# 3_Communication.net
KiCad netlist of a schematic drawn in Altium Designer
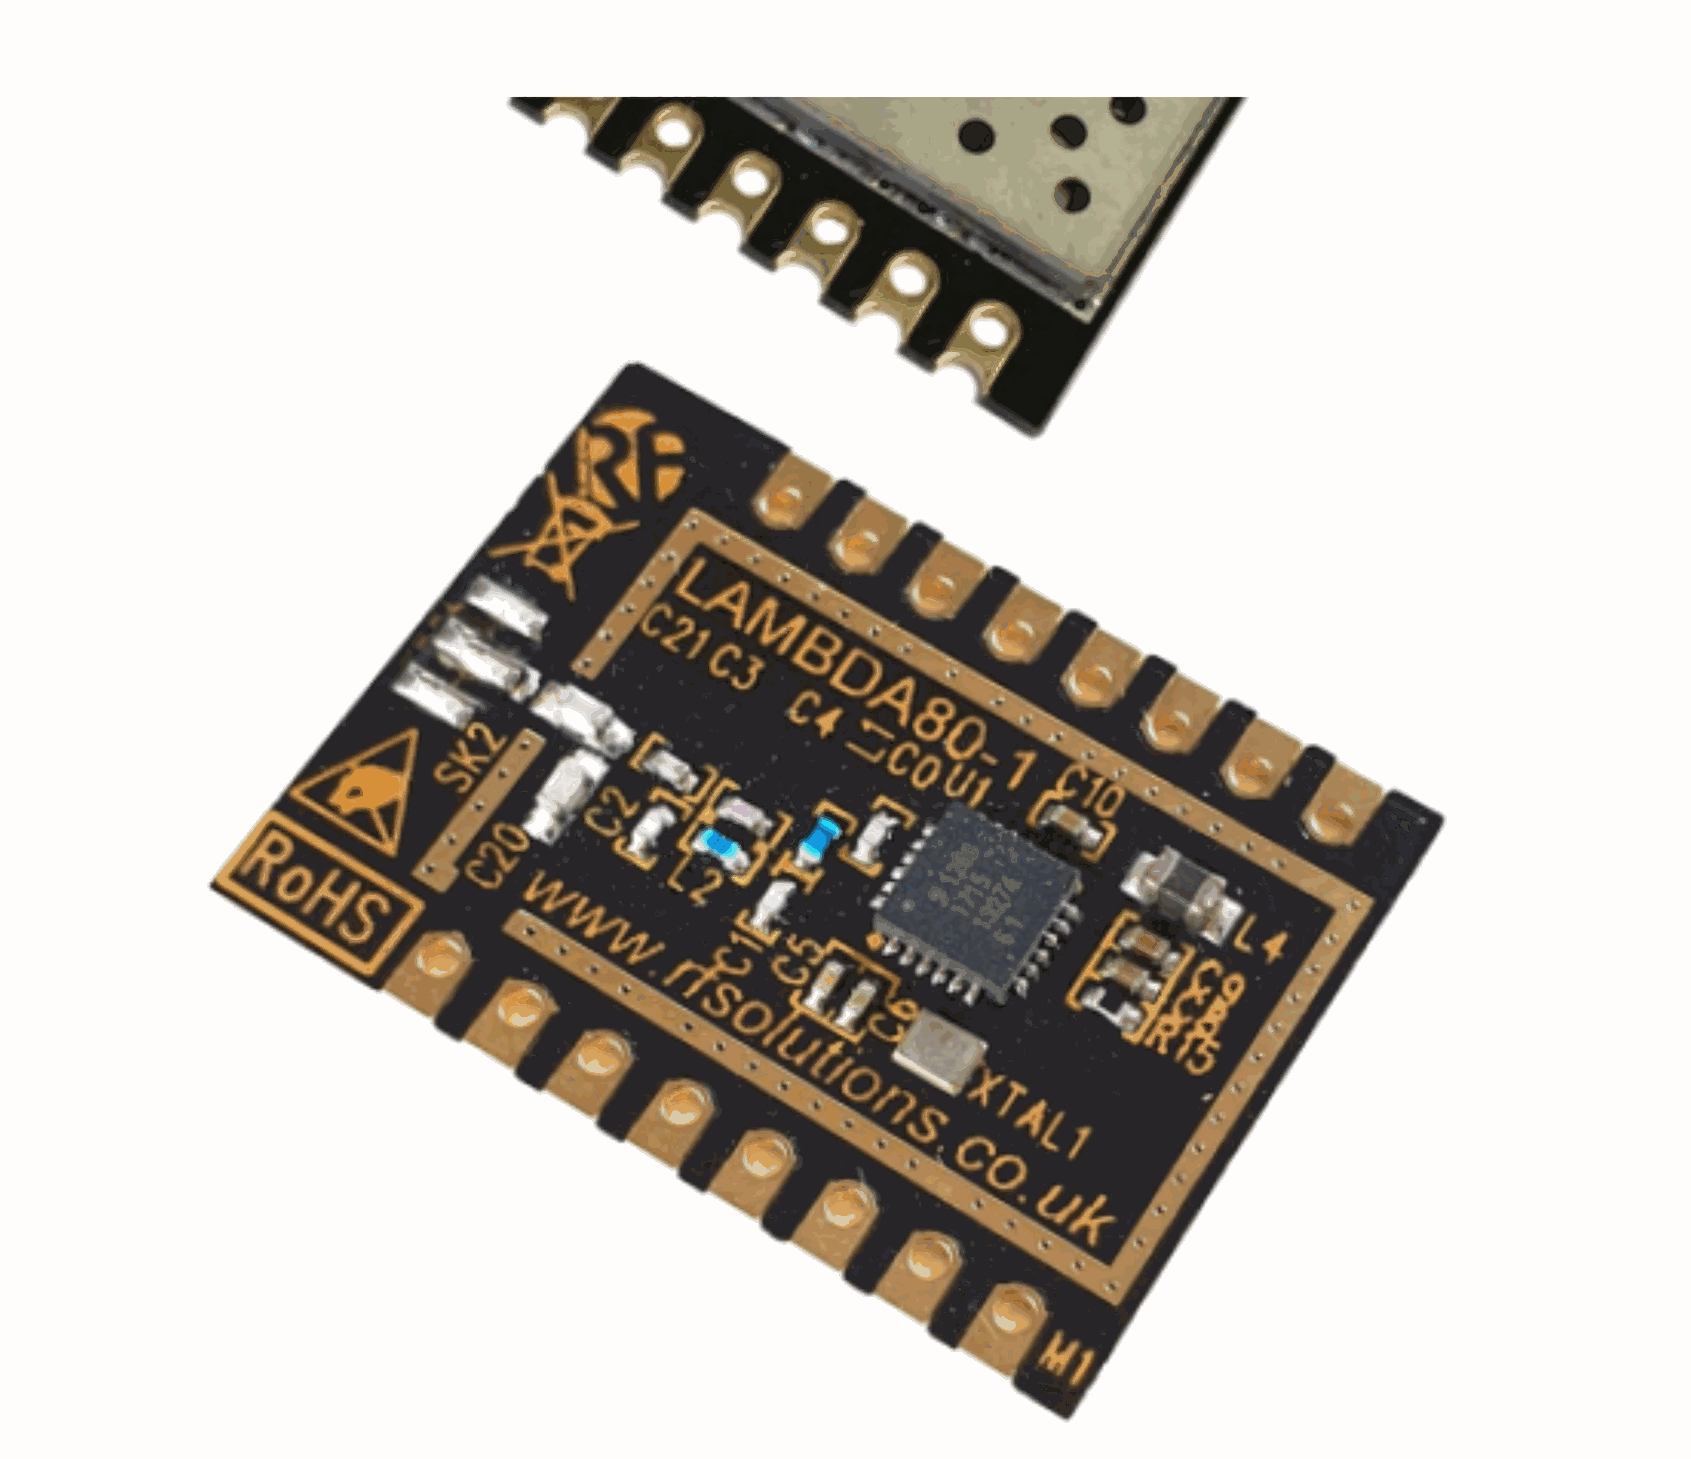
[diagram p0: 3_Communication.SchDoc, top middle]
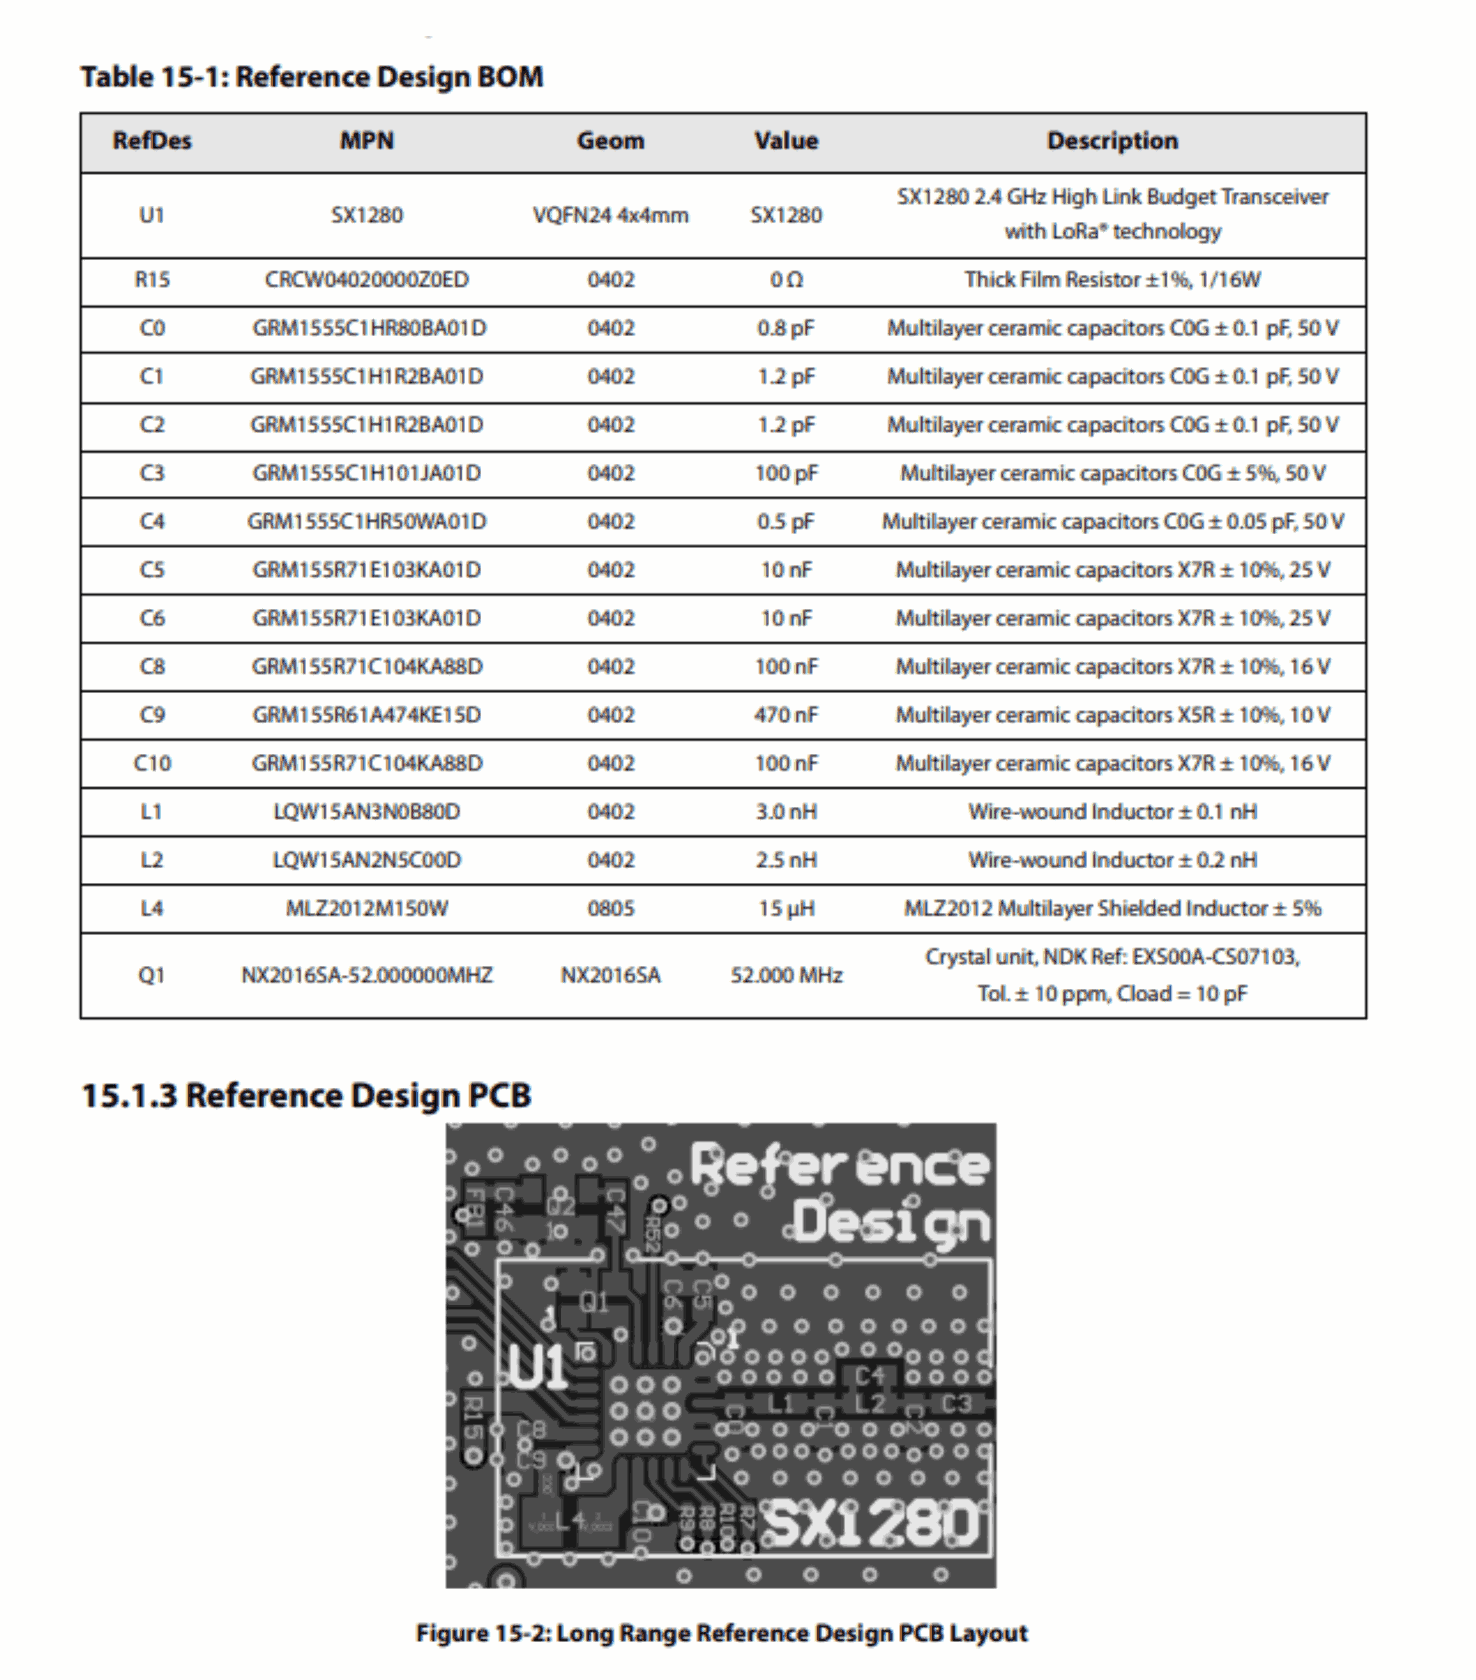
[diagram p1: 3_Communication.SchDoc, top right]
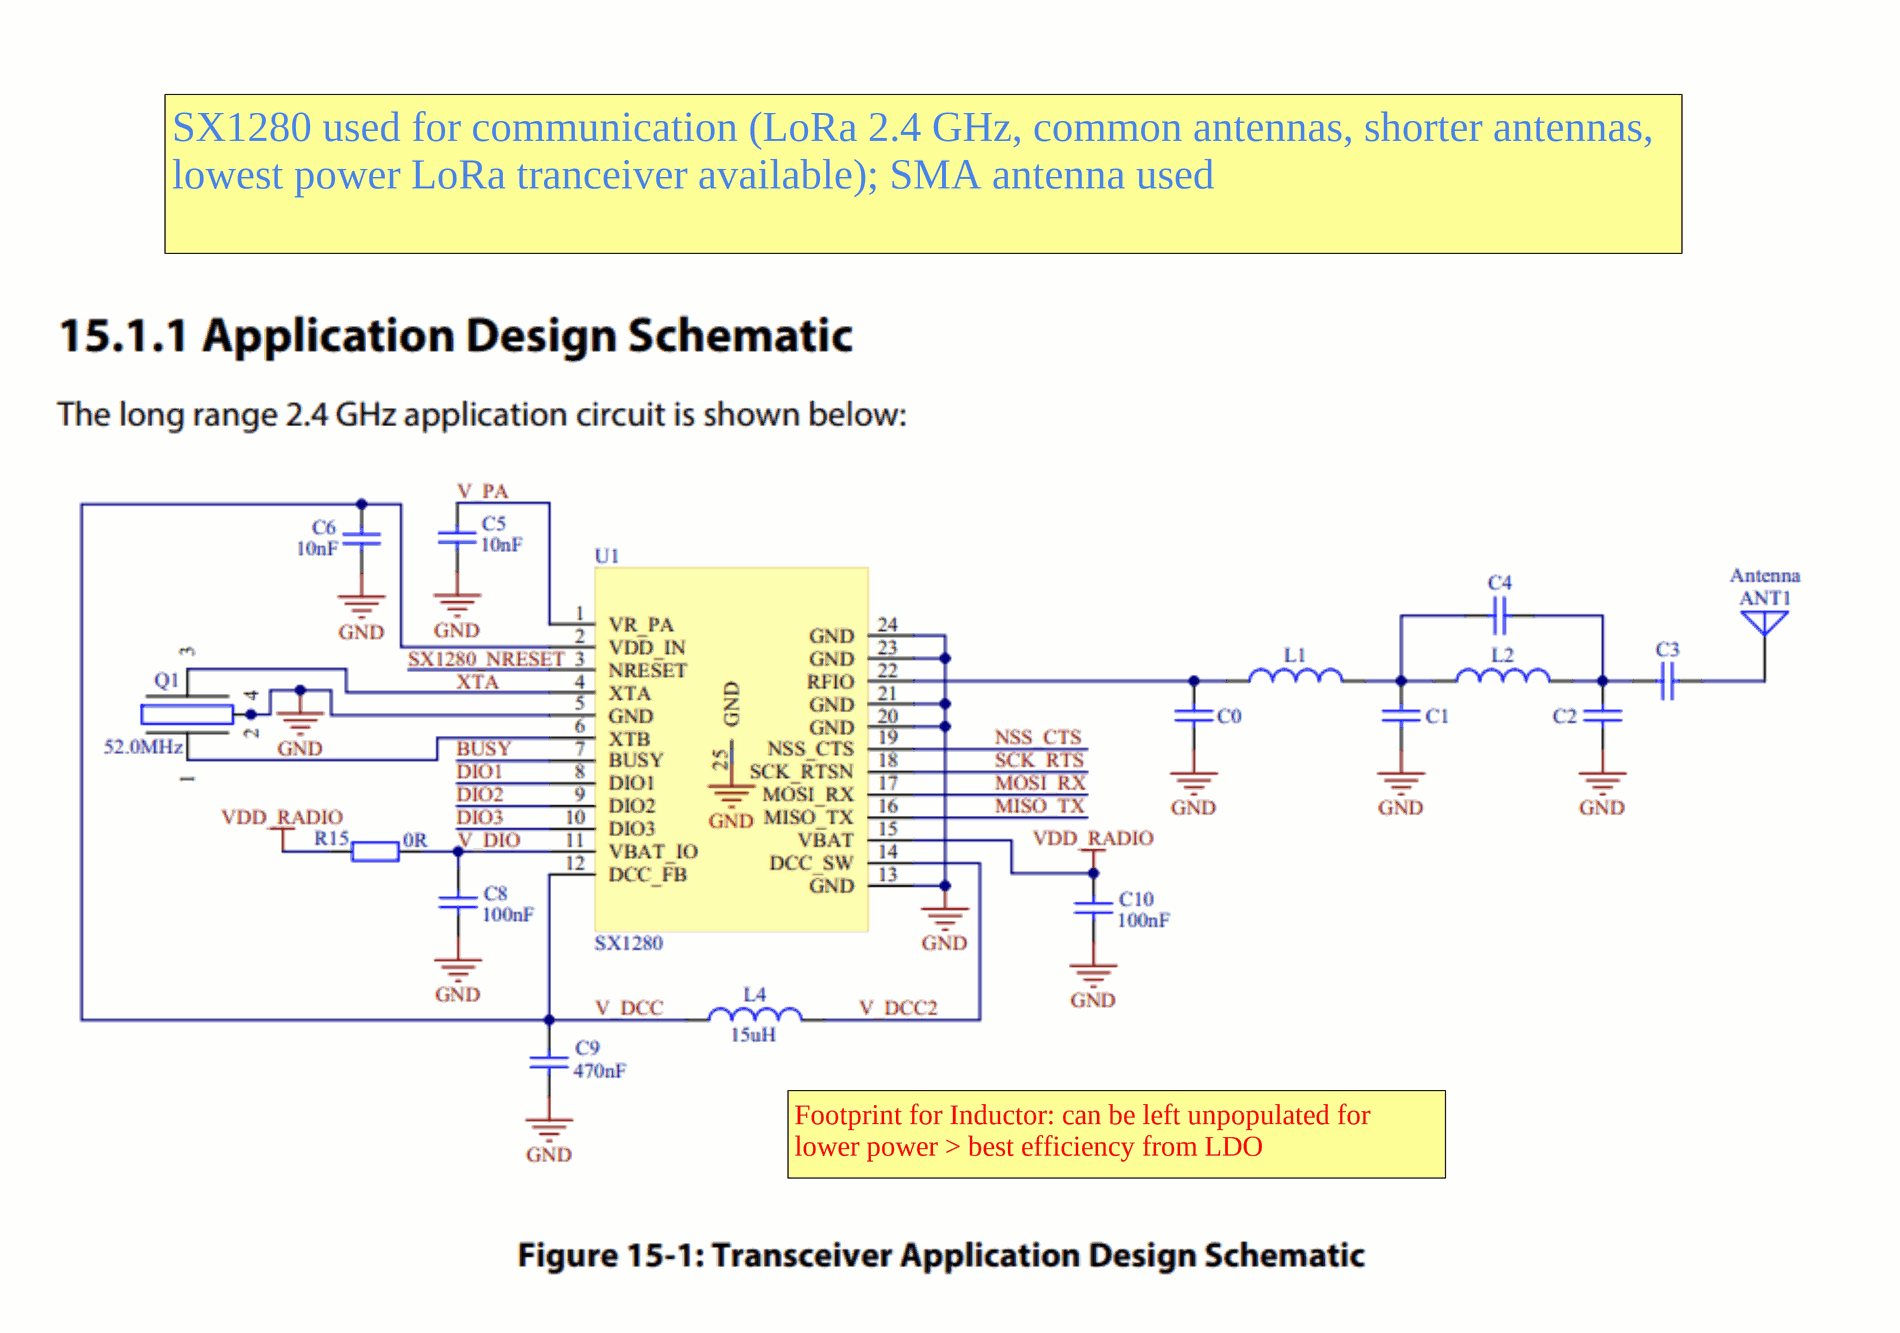
[diagram p2: 3_Communication.SchDoc, bottom left]
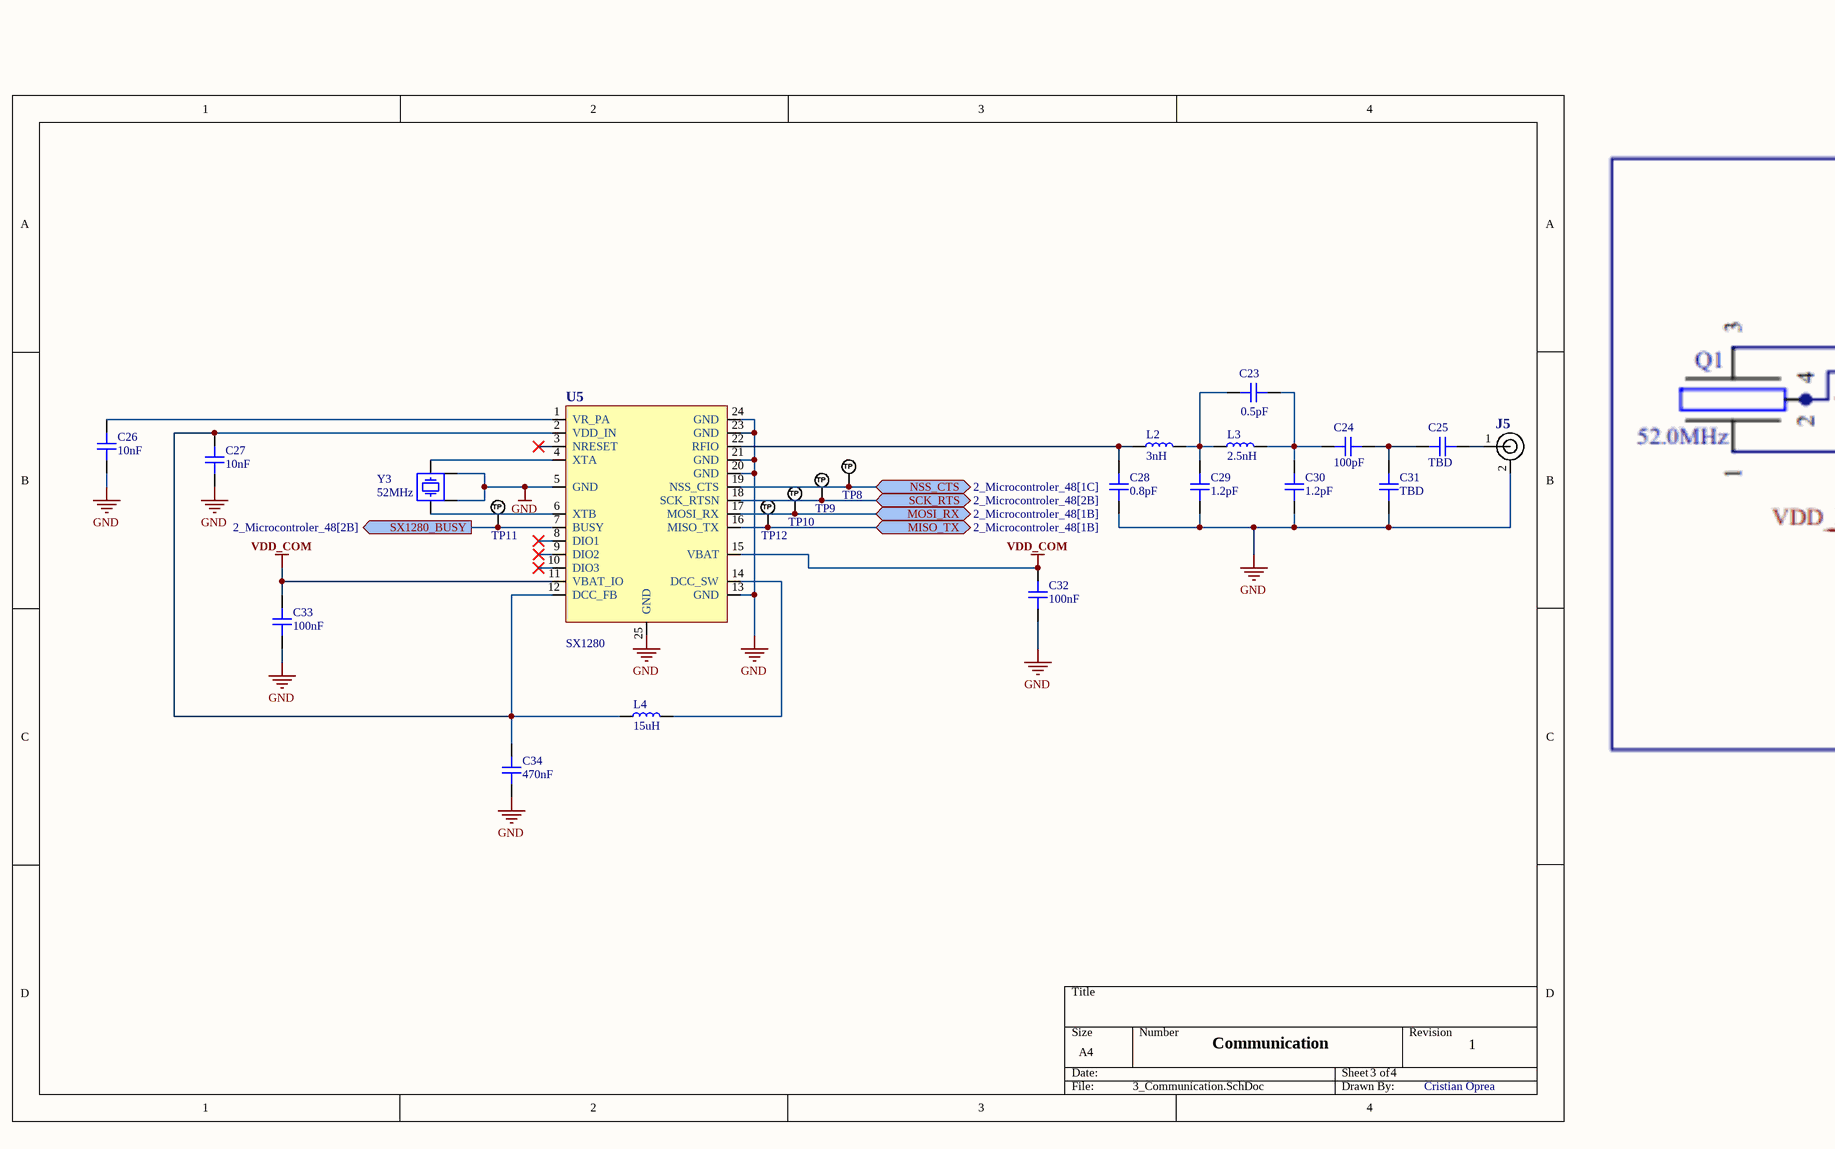
[diagram p3: 3_Communication.SchDoc, bottom middle]
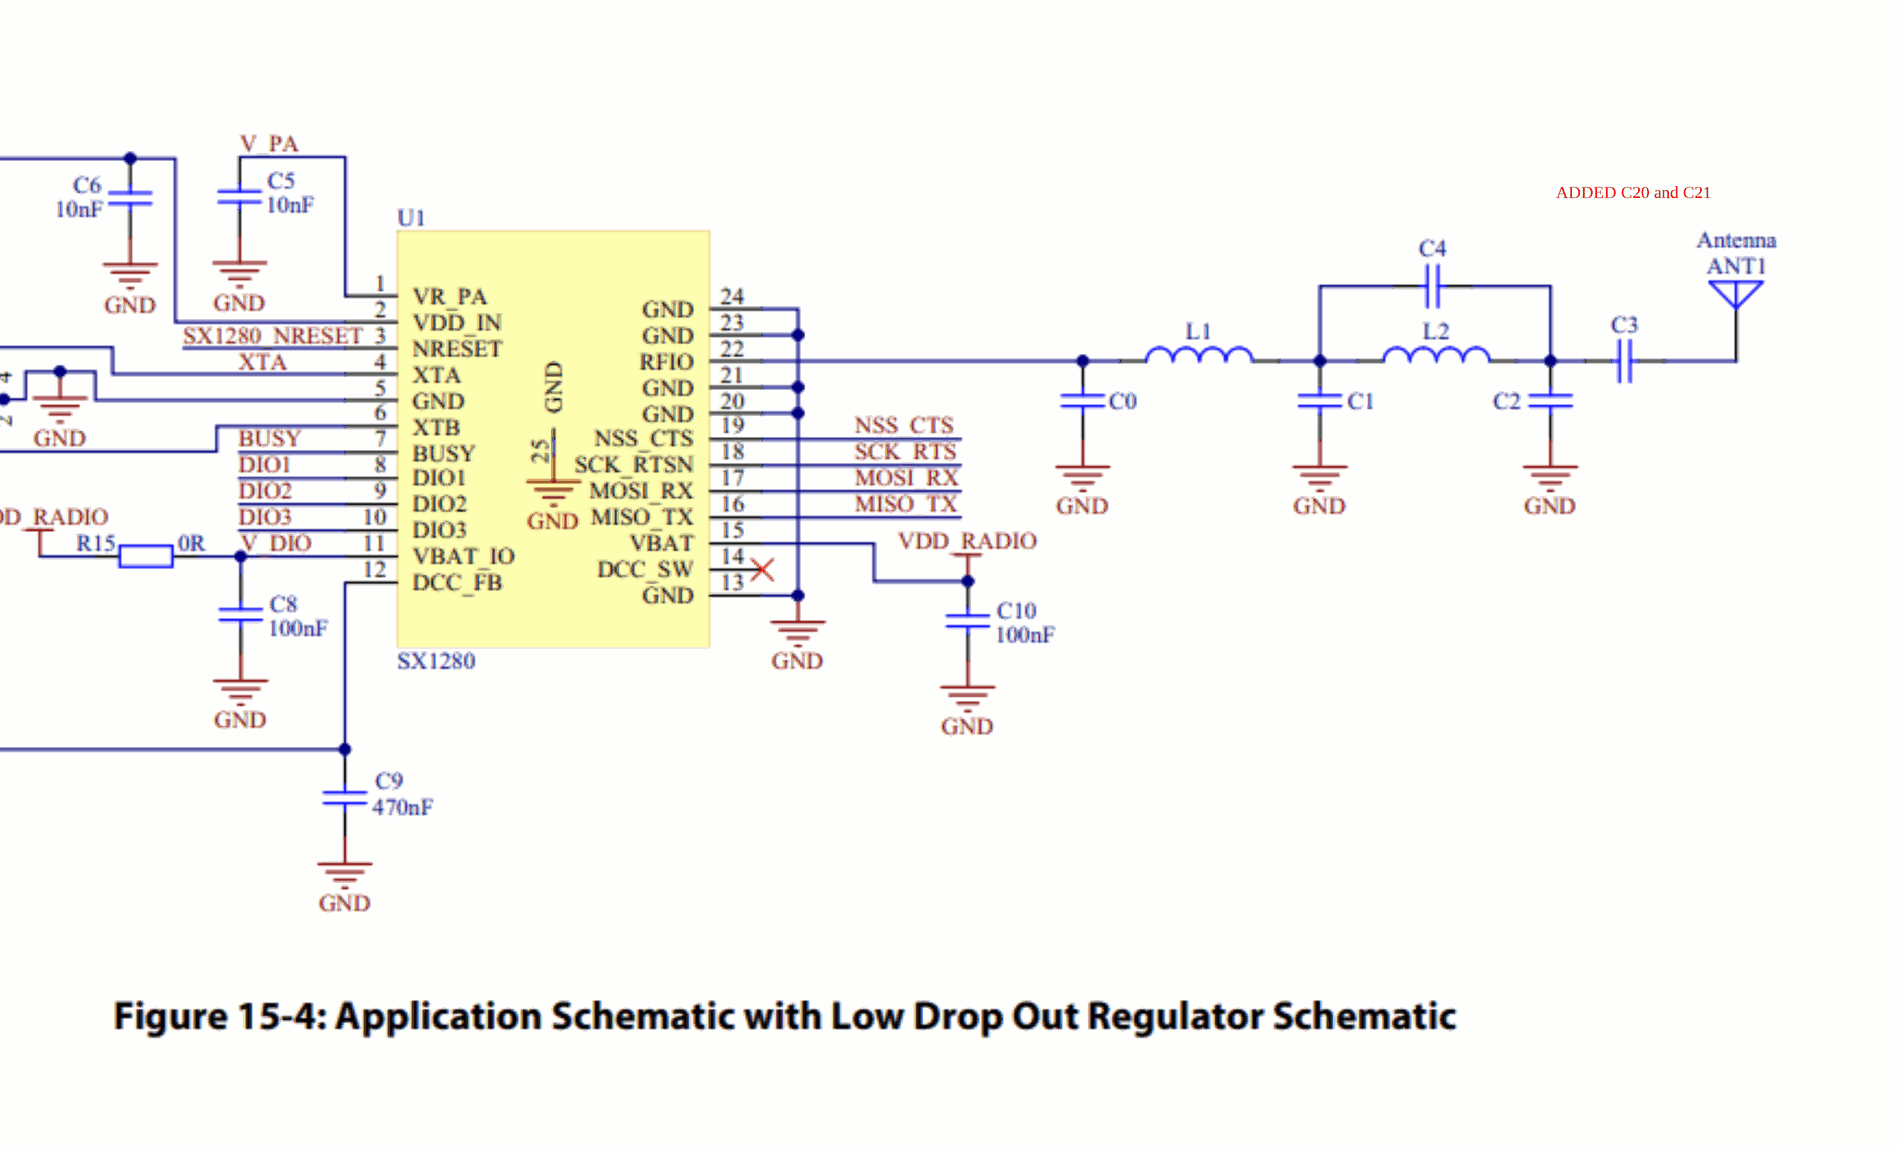
[diagram p4: 3_Communication.SchDoc, bottom right]

(export (version "E")
  (design (tool "Eeschema 10.0.6"))
  (components
    (comp (ref "C23")
      (value "0.5pF")
      (footprint "C0603")
      (description "Capacitor SMD 0603")
      (libsource (lib "Schlib_H2") (part "CAP_0603"))
    )
    (comp (ref "C24")
      (value "100pF")
      (footprint "C0603")
      (description "Capacitor SMD 0603")
      (libsource (lib "Schlib_H2") (part "CAP_0603"))
    )
    (comp (ref "C25")
      (value "TBD")
      (footprint "C0805")
      (description "Capacitor SMD 0805")
      (libsource (lib "Schlib_H2") (part "CAP_0603"))
    )
    (comp (ref "C26")
      (value "10nF")
      (footprint "C0603")
      (description "Capacitor SMD 0603")
      (libsource (lib "Schlib_H2") (part "CAP_0603"))
    )
    (comp (ref "C27")
      (value "10nF")
      (footprint "C0603")
      (description "Capacitor SMD 0603")
      (libsource (lib "Schlib_H2") (part "CAP_0603"))
    )
    (comp (ref "C28")
      (value "0.8pF")
      (footprint "C0603")
      (description "Capacitor SMD 0603")
      (libsource (lib "Schlib_H2") (part "CAP_0603"))
    )
    (comp (ref "C29")
      (value "1.2pF")
      (footprint "C0603")
      (description "Capacitor SMD 0603")
      (libsource (lib "Schlib_H2") (part "CAP_0603"))
    )
    (comp (ref "C30")
      (value "1.2pF")
      (footprint "C0603")
      (description "Capacitor SMD 0603")
      (libsource (lib "Schlib_H2") (part "CAP_0603"))
    )
    (comp (ref "C31")
      (value "TBD")
      (footprint "C0805")
      (description "Capacitor SMD 0805")
      (libsource (lib "Schlib_H2") (part "CAP_0603"))
    )
    (comp (ref "C32")
      (value "100nF")
      (footprint "C0603")
      (description "Capacitor SMD 0603")
      (libsource (lib "Schlib_H2") (part "CAP_0603"))
    )
    (comp (ref "C33")
      (value "100nF")
      (footprint "C0603")
      (description "Capacitor SMD 0603")
      (libsource (lib "Schlib_H2") (part "CAP_0603"))
    )
    (comp (ref "C34")
      (value "470nF")
      (footprint "C0603")
      (description "Capacitor SMD 0603")
      (libsource (lib "Schlib_H2") (part "CAP_0603"))
    )
    (comp (ref "J5")
      (value "SMA_EDGE_CONN")
      (footprint "CON_SMA-EDGE-S")
      (description "RF Connector SMA Female 50 Ohms 18 GHz PCB Edge Mount")
      (fields
        (field (name "MANUFACTURER") "RF Solutions")
        (field (name "MANUFACTURER PART NUMBER") "CON-SMA-EDGE-S")
      )
      (libsource (lib "Schlib_H2") (part "CON-SMA-EDGE-S"))
    )
    (comp (ref "L2")
      (value "3nH")
      (footprint "R0603")
      (description "Inductor SMD 0603")
      (libsource (lib "Schlib_H2") (part "IND_0603"))
    )
    (comp (ref "L3")
      (value "2.5nH")
      (footprint "R0603")
      (description "Inductor SMD 0603")
      (libsource (lib "Schlib_H2") (part "IND_0603"))
    )
    (comp (ref "L4")
      (value "15uH")
      (footprint "IND_3.2_4")
      (description "Inductor SMD 0603")
      (libsource (lib "Schlib_H2") (part "IND_0603"))
    )
    (comp (ref "TP8")
      (value "TP_NOBOM")
      (footprint "TEST_PAD_THD")
      (description "Test Point Round 1mm (NO BOM)")
      (libsource (lib "Schlib_H2") (part "TEST_POINT_RND_1MM"))
    )
    (comp (ref "TP9")
      (value "TP_NOBOM")
      (footprint "TEST_PAD_THD")
      (description "Test Point Round 1mm (NO BOM)")
      (libsource (lib "Schlib_H2") (part "TEST_POINT_RND_1MM"))
    )
    (comp (ref "TP10")
      (value "TP_NOBOM")
      (footprint "TEST_PAD_THD")
      (description "Test Point Round 1mm (NO BOM)")
      (libsource (lib "Schlib_H2") (part "TEST_POINT_RND_1MM"))
    )
    (comp (ref "TP11")
      (value "TP_NOBOM")
      (footprint "TEST_PAD_THD")
      (description "Test Point Round 1mm (NO BOM)")
      (libsource (lib "Schlib_H2") (part "TEST_POINT_RND_1MM"))
    )
    (comp (ref "TP12")
      (value "TP_NOBOM")
      (footprint "TEST_PAD_THD")
      (description "Test Point Round 1mm (NO BOM)")
      (libsource (lib "Schlib_H2") (part "TEST_POINT_RND_1MM"))
    )
    (comp (ref "U5")
      (value "SX1280")
      (footprint "QFN-24_4x4_0.5")
      (description "Low power LoRa transceiver operating at 2.4GHz with ranging capability")
      (libsource (lib "Schlib_H2") (part "SX1280"))
    )
    (comp (ref "Y3")
      (value "52MHz")
      (footprint "CRYSTAL_2016_4P")
      (description "Crystal")
      (fields
        (field (name "MANUFACTURER") "Epson")
        (field (name "MANUFACTURER PART NUMBER") "TSX-3225 24.0000MF15X-AC")
      )
      (libsource (lib "Schlib_H2") (part "Crystal"))
    )
  )
  (nets
    (net (code "1") (name "/MISO_TX") (class "Default")
      (node (ref "TP12") (pin "1") (pinfunction "TP_1") (pintype "passive"))
      (node (ref "U5") (pin "16") (pinfunction "MISO_TX_16") (pintype "passive"))
    )
    (net (code "2") (name "/MOSI_RX") (class "Default")
      (node (ref "TP10") (pin "1") (pinfunction "TP_1") (pintype "passive"))
      (node (ref "U5") (pin "17") (pinfunction "MOSI_RX_17") (pintype "passive"))
    )
    (net (code "3") (name "/NSS_CTS") (class "Default")
      (node (ref "TP8") (pin "1") (pinfunction "TP_1") (pintype "passive"))
      (node (ref "U5") (pin "19") (pinfunction "NSS_CTS_19") (pintype "passive"))
    )
    (net (code "4") (name "/SCK_RTS") (class "Default")
      (node (ref "TP9") (pin "1") (pinfunction "TP_1") (pintype "passive"))
      (node (ref "U5") (pin "18") (pinfunction "SCK_RTSN_18") (pintype "passive"))
    )
    (net (code "5") (name "/SX1280_BUSY") (class "Default")
      (node (ref "TP11") (pin "1") (pinfunction "TP_1") (pintype "passive"))
      (node (ref "U5") (pin "7") (pinfunction "BUSY_7") (pintype "passive"))
    )
    (net (code "6") (name "GND") (class "Default")
      (node (ref "C26") (pin "1") (pinfunction "1_1") (pintype "passive"))
      (node (ref "C27") (pin "1") (pinfunction "1_1") (pintype "passive"))
      (node (ref "C28") (pin "1") (pinfunction "1_1") (pintype "passive"))
      (node (ref "C29") (pin "1") (pinfunction "1_1") (pintype "passive"))
      (node (ref "C30") (pin "1") (pinfunction "1_1") (pintype "passive"))
      (node (ref "C31") (pin "1") (pinfunction "1_1") (pintype "passive"))
      (node (ref "C32") (pin "1") (pinfunction "1_1") (pintype "passive"))
      (node (ref "C33") (pin "1") (pinfunction "1_1") (pintype "passive"))
      (node (ref "C34") (pin "1") (pinfunction "1_1") (pintype "passive"))
      (node (ref "J5") (pin "2") (pinfunction "2_2") (pintype "passive"))
      (node (ref "U5") (pin "13") (pinfunction "GND_13") (pintype "passive"))
      (node (ref "U5") (pin "20") (pinfunction "GND_20") (pintype "passive"))
      (node (ref "U5") (pin "21") (pinfunction "GND_21") (pintype "passive"))
      (node (ref "U5") (pin "23") (pinfunction "GND_23") (pintype "passive"))
      (node (ref "U5") (pin "24") (pinfunction "GND_24") (pintype "passive"))
      (node (ref "U5") (pin "25") (pinfunction "GND_25") (pintype "passive"))
      (node (ref "U5") (pin "5") (pinfunction "GND_5") (pintype "passive"))
      (node (ref "Y3") (pin "2") (pinfunction "2_2") (pintype "passive"))
      (node (ref "Y3") (pin "4") (pinfunction "4_4") (pintype "passive"))
    )
    (net (code "7") (name "Net-(C23-Pad1)") (class "Default")
      (node (ref "C23") (pin "1") (pinfunction "1_1") (pintype "passive"))
      (node (ref "C24") (pin "2") (pinfunction "2_2") (pintype "passive"))
      (node (ref "C30") (pin "2") (pinfunction "2_2") (pintype "passive"))
      (node (ref "L3") (pin "2") (pinfunction "2_2") (pintype "passive"))
    )
    (net (code "8") (name "Net-(C23-Pad2)") (class "Default")
      (node (ref "C23") (pin "2") (pinfunction "2_2") (pintype "passive"))
      (node (ref "C29") (pin "2") (pinfunction "2_2") (pintype "passive"))
      (node (ref "L2") (pin "2") (pinfunction "2_2") (pintype "passive"))
      (node (ref "L3") (pin "1") (pinfunction "1_1") (pintype "passive"))
    )
    (net (code "9") (name "Net-(C24-Pad1)") (class "Default")
      (node (ref "C24") (pin "1") (pinfunction "1_1") (pintype "passive"))
      (node (ref "C25") (pin "2") (pinfunction "2_2") (pintype "passive"))
      (node (ref "C31") (pin "2") (pinfunction "2_2") (pintype "passive"))
    )
    (net (code "10") (name "Net-(C25-Pad1)") (class "Default")
      (node (ref "C25") (pin "1") (pinfunction "1_1") (pintype "passive"))
      (node (ref "J5") (pin "1") (pinfunction "1_1") (pintype "passive"))
    )
    (net (code "11") (name "Net-(U5-DCC_FB)") (class "Default")
      (node (ref "C27") (pin "2") (pinfunction "2_2") (pintype "passive"))
      (node (ref "C34") (pin "2") (pinfunction "2_2") (pintype "passive"))
      (node (ref "L4") (pin "1") (pinfunction "1_1") (pintype "passive"))
      (node (ref "U5") (pin "12") (pinfunction "DCC_FB_12") (pintype "passive"))
      (node (ref "U5") (pin "2") (pinfunction "VDD_IN_2") (pintype "passive"))
    )
    (net (code "12") (name "Net-(U5-DCC_SW)") (class "Default")
      (node (ref "L4") (pin "2") (pinfunction "2_2") (pintype "passive"))
      (node (ref "U5") (pin "14") (pinfunction "DCC_SW_14") (pintype "passive"))
    )
    (net (code "13") (name "Net-(U5-RFIO)") (class "Default")
      (node (ref "C28") (pin "2") (pinfunction "2_2") (pintype "passive"))
      (node (ref "L2") (pin "1") (pinfunction "1_1") (pintype "passive"))
      (node (ref "U5") (pin "22") (pinfunction "RFIO_22") (pintype "passive"))
    )
    (net (code "14") (name "Net-(U5-VR_PA)") (class "Default")
      (node (ref "C26") (pin "2") (pinfunction "2_2") (pintype "passive"))
      (node (ref "U5") (pin "1") (pinfunction "VR_PA_1") (pintype "passive"))
    )
    (net (code "15") (name "Net-(U5-XTA)") (class "Default")
      (node (ref "U5") (pin "4") (pinfunction "XTA_4") (pintype "passive"))
      (node (ref "Y3") (pin "3") (pinfunction "3_3") (pintype "passive"))
    )
    (net (code "16") (name "Net-(U5-XTB)") (class "Default")
      (node (ref "U5") (pin "6") (pinfunction "XTB_6") (pintype "passive"))
      (node (ref "Y3") (pin "1") (pinfunction "1_1") (pintype "passive"))
    )
    (net (code "17") (name "VDD_COM") (class "Default")
      (node (ref "C32") (pin "2") (pinfunction "2_2") (pintype "passive"))
      (node (ref "C33") (pin "2") (pinfunction "2_2") (pintype "passive"))
      (node (ref "U5") (pin "11") (pinfunction "VBAT_IO_11") (pintype "passive"))
      (node (ref "U5") (pin "15") (pinfunction "VBAT_15") (pintype "passive"))
    )
    (net (code "18") (name "unconnected-(U5-DIO1-Pad8)") (class "Default")
      (node (ref "U5") (pin "8") (pinfunction "DIO1_8") (pintype "passive+no_connect"))
    )
    (net (code "19") (name "unconnected-(U5-DIO2-Pad9)") (class "Default")
      (node (ref "U5") (pin "9") (pinfunction "DIO2_9") (pintype "passive+no_connect"))
    )
    (net (code "20") (name "unconnected-(U5-DIO3-Pad10)") (class "Default")
      (node (ref "U5") (pin "10") (pinfunction "DIO3_10") (pintype "passive+no_connect"))
    )
    (net (code "21") (name "unconnected-(U5-NRESET-Pad3)") (class "Default")
      (node (ref "U5") (pin "3") (pinfunction "NRESET_3") (pintype "passive+no_connect"))
    )
  )
)
